# Voeding.net
KiCad netlist of a schematic drawn in Altium Designer
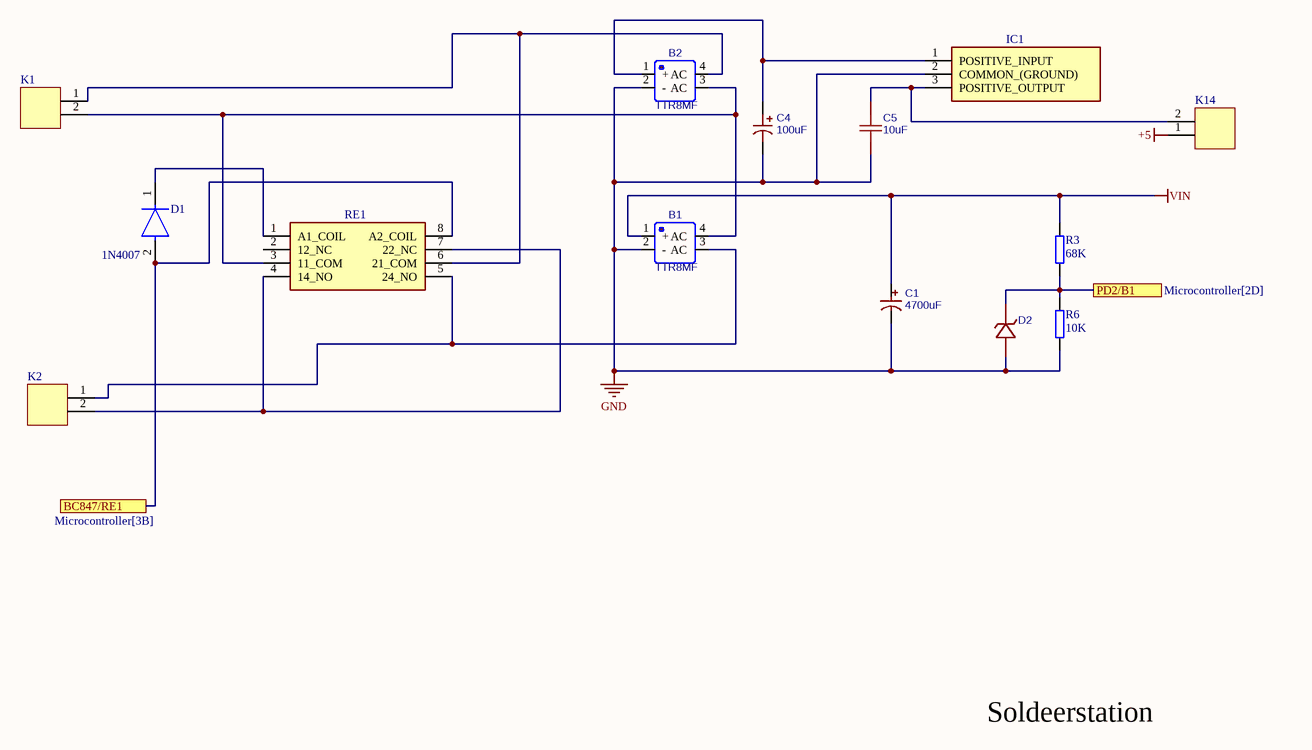
[diagram p0: Voeding.SchDoc]

(export (version "E")
  (design (tool "Eeschema 10.0.6"))
  (components
    (comp (ref "B1")
      (value "TTR8MF")
      (footprint "B1,2 Brug gelijkrichter")
      (fields (field (name "BOM_SUPPLIER PART") "C712546") (field (name "CONTRIBUTOR") "LCSC"))
      (libsource (lib "SoldeerStation") (part "B1,2 Brug Gelijkrichter"))
    )
    (comp (ref "B2")
      (value "TTR8MF")
      (footprint "B1,2 Brug gelijkrichter")
      (fields (field (name "BOM_SUPPLIER PART") "C712546") (field (name "CONTRIBUTOR") "LCSC"))
      (libsource (lib "SoldeerStation") (part "B1,2 Brug Gelijkrichter"))
    )
    (comp (ref "C1")
      (value "4700uF")
      (footprint "C1 4700uF")
      (fields
        (field (name "BOM_MANUFACTURER PART") "KM478M050N35RR0VH2FP0")
        (field (name "BOM_SUPPLIER PART") "C45662")
      )
      (libsource (lib "SoldeerStation") (part "C1 4700uF"))
    )
    (comp (ref "C4")
      (value "100uF")
      (footprint "C4 100uF")
      (fields
        (field (name "BOM_SUPPLIER PART") "C445063")
        (field (name "BOM_MANUFACTURER PART") "UWT1H101MNL1GS")
        (field (name "CONTRIBUTOR") "LCSC")
      )
      (libsource (lib "SoldeerStation") (part "C4 100uF"))
    )
    (comp (ref "C5")
      (value "10uF")
      (footprint "C2,5,10 10uF")
      (fields
        (field (name "BOM_SUPPLIER PART") "C440198")
        (field (name "BOM_MANUFACTURER PART") "GRM21BR61H106KE43L")
        (field (name "CONTRIBUTOR") "LCSC")
      )
      (libsource (lib "SoldeerStation") (part "C2,5,10 10uF"))
    )
    (comp (ref "D1")
      (value "1N4007")
      (footprint "FP-1N4007-MFG")
      (description "DIODE GEN PURP 1KV 1A DO204AL")
      (fields
        (field (name "OCTOPART") "https://octopart.com/1n4007-e3%2F54-vishay-39548207")
        (field (name "MANUFACTURER") "Vishay")
      )
      (libsource (lib "SoldeerStation") (part "zo_1N4007"))
    )
    (comp (ref "D2")
      (value "~")
      (footprint "D2 zener diode")
      (description "BZT52C5V1_C1884555")
      (fields
        (field (name "BOM_SUPPLIER PART") "C1884555")
        (field (name "BOM_MANUFACTURER PART") "BZT52C5V1")
        (field (name "CONTRIBUTOR") "LCSC")
      )
      (libsource (lib "SoldeerStation") (part "D2 zener diode"))
    )
    (comp (ref "IC1")
      (value "~")
      (footprint "IC1 DC-DC converter")
      (description "Non-Isolated DC/DC Converters 7.5W 24Vin 5Vout1 1.5A SIP Non-Iso")
      (fields
        (field (name "MOUSER PART NUMBER") "580-OKI78SR5/1.5W36C")
        (field (name "MANUFACTURER_PART_NUMBER") "OKI-78SR-5/1.5-W36-C")
      )
      (libsource (lib "SoldeerStation") (part "IC1 OKI-78SR-5_1.5-W36-C"))
    )
    (comp (ref "K1")
      (value "~")
      (footprint "Terminal_2")
      (libsource (lib "SoldeerStation") (part "K Terminal_2"))
    )
    (comp (ref "K2")
      (value "~")
      (footprint "Terminal_2")
      (libsource (lib "SoldeerStation") (part "K Terminal_2"))
    )
    (comp (ref "K14")
      (value "~")
      (footprint "PInHeader_2")
      (libsource (lib "SoldeerStation") (part "K PinHeader_2"))
    )
    (comp (ref "R3")
      (value "68K")
      (footprint "RESC2013X50X30ML20T20")
      (fields (field (name "MANUFACTURER") "Vishay Dale") (field (name "PART NUMBER") "CRCW08050000Z0EA"))
      (libsource (lib "SoldeerStation") (part "R Resistor"))
    )
    (comp (ref "R6")
      (value "10K")
      (footprint "RESC2013X50X30ML20T20")
      (fields (field (name "MANUFACTURER") "Vishay Dale") (field (name "PART NUMBER") "CRCW08050000Z0EA"))
      (libsource (lib "SoldeerStation") (part "R Resistor"))
    )
    (comp (ref "RE1")
      (value "~")
      (footprint "RE1 Vermogen relais")
      (description "RT424005F  General Purpose Relays DPDT 8A 5VDC GEN PURPOSE RELAY")
      (fields
        (field (name "MOUSER PART NUMBER") "655-RT424005F")
        (field (name "MANUFACTURER_PART_NUMBER") "RT424005F")
      )
      (libsource (lib "SoldeerStation") (part "RE1 Vermogen relais"))
    )
  )
  (nets
    (net (code "1") (name "+5") (class "Default") (node (ref "K14") (pin "1") (pintype "passive")))
    (net (code "2") (name "/BC847{slash}RE1") (class "Default")
      (node (ref "D1") (pin "2") (pinfunction "A_2") (pintype "passive"))
      (node (ref "RE1") (pin "8") (pinfunction "A2_COIL_8") (pintype "passive"))
    )
    (net (code "3") (name "/PD2{slash}B1") (class "Default")
      (node (ref "D2") (pin "1") (pinfunction "K_1") (pintype "passive"))
      (node (ref "R3") (pin "1") (pinfunction "1_1") (pintype "passive"))
      (node (ref "R6") (pin "2") (pinfunction "2_2") (pintype "passive"))
    )
    (net (code "4") (name "GND") (class "Default")
      (node (ref "B1") (pin "2") (pinfunction "-_2") (pintype "passive"))
      (node (ref "B2") (pin "2") (pinfunction "-_2") (pintype "passive"))
      (node (ref "C1") (pin "2") (pinfunction "2_2") (pintype "passive"))
      (node (ref "C4") (pin "2") (pinfunction "2_2") (pintype "passive"))
      (node (ref "C5") (pin "1") (pinfunction "1_1") (pintype "passive"))
      (node (ref "D2") (pin "2") (pinfunction "A_2") (pintype "passive"))
      (node (ref "IC1") (pin "2") (pinfunction "COMMON_(GROUND)_2") (pintype "passive"))
      (node (ref "R6") (pin "1") (pinfunction "1_1") (pintype "passive"))
    )
    (net (code "5") (name "Net-(B2-+)") (class "Default")
      (node (ref "B2") (pin "1") (pinfunction "+_1") (pintype "passive"))
      (node (ref "C4") (pin "1") (pinfunction "1_1") (pintype "passive"))
      (node (ref "IC1") (pin "1") (pinfunction "POSITIVE_INPUT_1") (pintype "passive"))
    )
    (net (code "6") (name "Net-(D1-C)") (class "Default")
      (node (ref "D1") (pin "1") (pinfunction "C_1") (pintype "passive"))
      (node (ref "RE1") (pin "1") (pinfunction "A1_COIL_1") (pintype "passive"))
    )
    (net (code "7") (name "Net-(IC1-POSITIVE_OUTPUT)") (class "Default")
      (node (ref "C5") (pin "2") (pinfunction "2_2") (pintype "passive"))
      (node (ref "IC1") (pin "3") (pinfunction "POSITIVE_OUTPUT_3") (pintype "passive"))
      (node (ref "K14") (pin "2") (pintype "passive"))
    )
    (net (code "8") (name "Net-(RE1-11_COM)") (class "Default")
      (node (ref "B1") (pin "4") (pinfunction "AC_4") (pintype "passive"))
      (node (ref "B2") (pin "3") (pinfunction "AC_3") (pintype "passive"))
      (node (ref "K1") (pin "2") (pintype "passive"))
      (node (ref "RE1") (pin "3") (pinfunction "11_COM_3") (pintype "passive"))
    )
    (net (code "9") (name "Net-(RE1-14_NO)") (class "Default")
      (node (ref "K2") (pin "2") (pintype "passive"))
      (node (ref "RE1") (pin "4") (pinfunction "14_NO_4") (pintype "passive"))
      (node (ref "RE1") (pin "7") (pinfunction "22_NC_7") (pintype "passive"))
    )
    (net (code "10") (name "Net-(RE1-21_COM)") (class "Default")
      (node (ref "B2") (pin "4") (pinfunction "AC_4") (pintype "passive"))
      (node (ref "K1") (pin "1") (pintype "passive"))
      (node (ref "RE1") (pin "6") (pinfunction "21_COM_6") (pintype "passive"))
    )
    (net (code "11") (name "Net-(RE1-24_NO)") (class "Default")
      (node (ref "B1") (pin "3") (pinfunction "AC_3") (pintype "passive"))
      (node (ref "K2") (pin "1") (pintype "passive"))
      (node (ref "RE1") (pin "5") (pinfunction "24_NO_5") (pintype "passive"))
    )
    (net (code "12") (name "VIN") (class "Default")
      (node (ref "B1") (pin "1") (pinfunction "+_1") (pintype "passive"))
      (node (ref "C1") (pin "1") (pinfunction "1_1") (pintype "passive"))
      (node (ref "R3") (pin "2") (pinfunction "2_2") (pintype "passive"))
    )
    (net (code "13") (name "unconnected-(RE1-12_NC-Pad2)") (class "Default")
      (node (ref "RE1") (pin "2") (pinfunction "12_NC_2") (pintype "passive"))
    )
  )
)
